# Thermal_Stage_rev4_xml.net
KiCad netlist of a schematic drawn in EAGLE
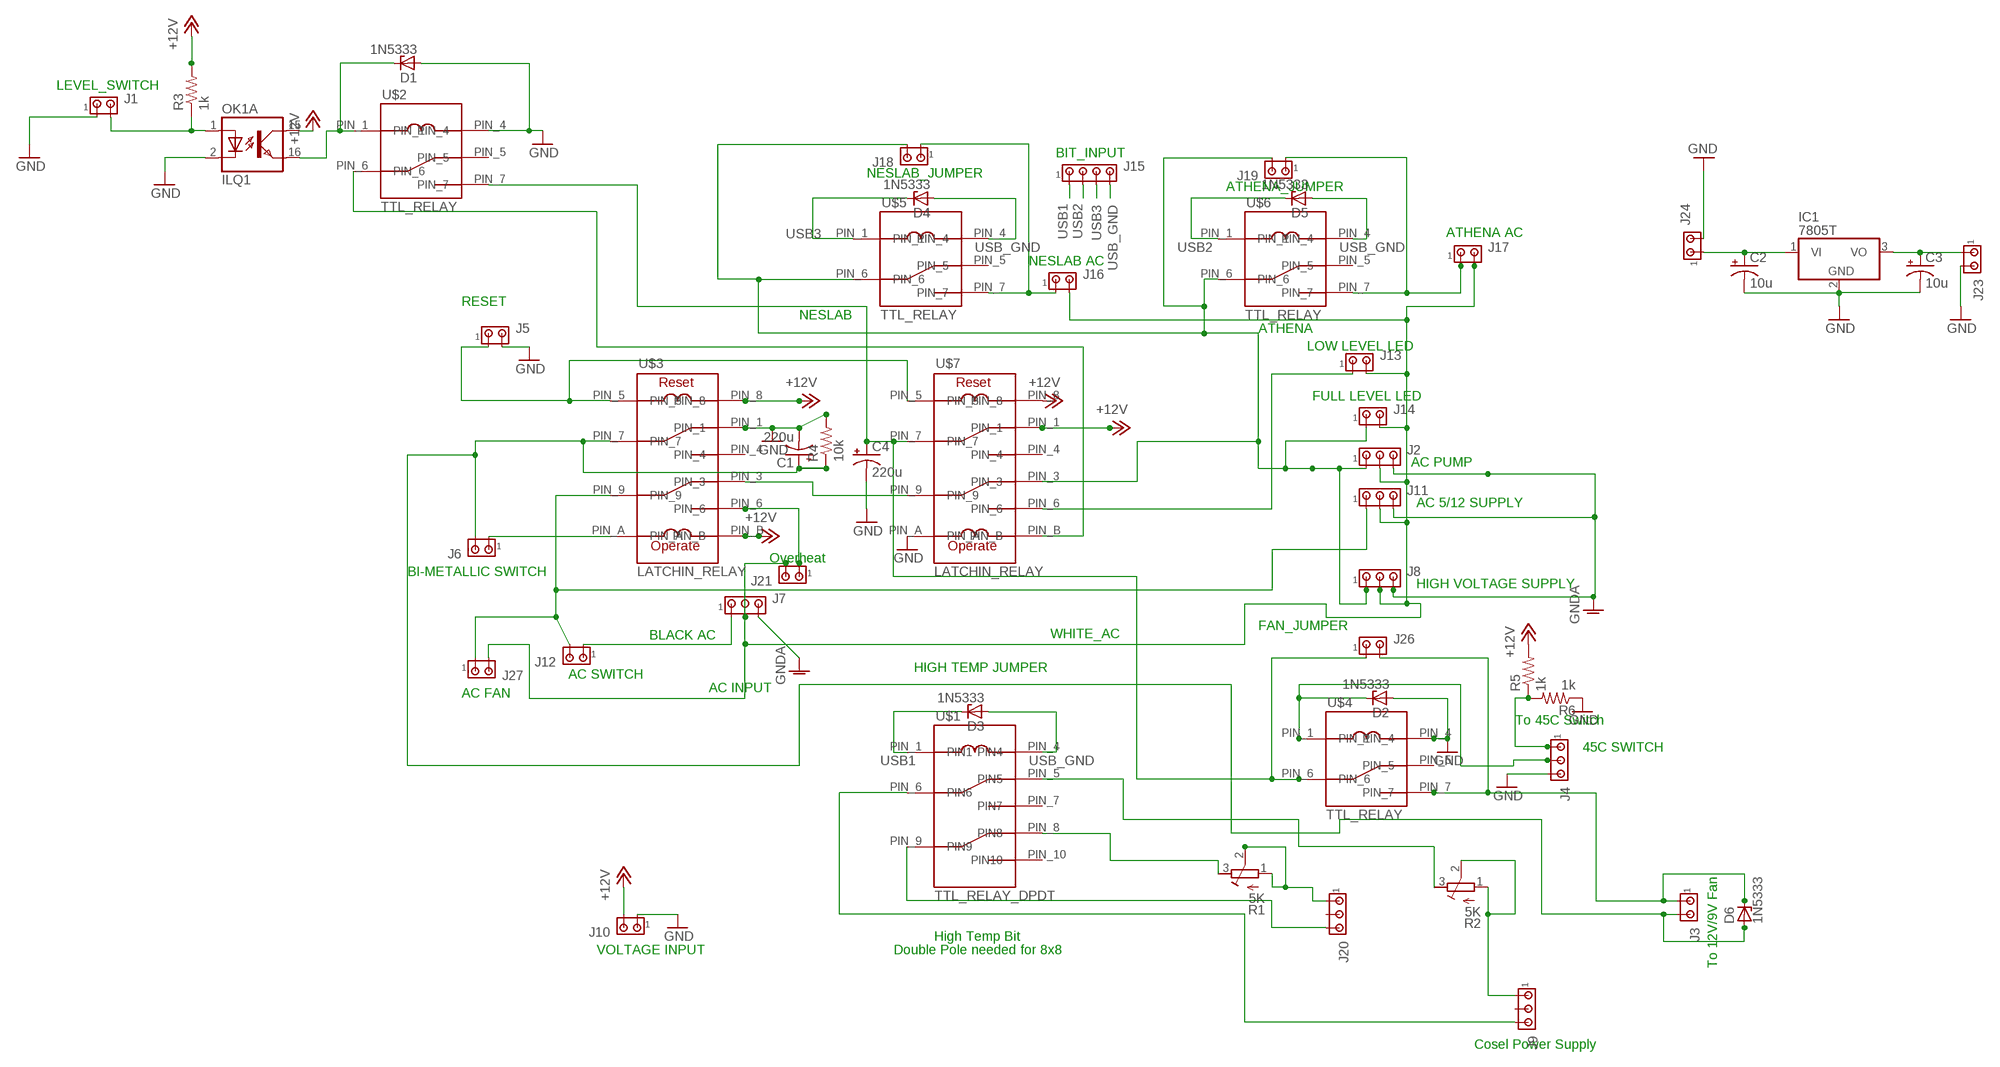
[diagram p0: schematic, sheet 1]

(export (version "E")
  (design (tool "Eeschema 10.0.6"))
  (components
    (comp (ref "C1")
      (value "220u")
      (footprint "eagle-import:E5-13")
      (libsource (lib "eagle-import") (part "CPOL-USE5-13"))
    )
    (comp (ref "C2")
      (value "10u")
      (footprint "eagle-import:E2,5-6E")
      (libsource (lib "eagle-import") (part "CPOL-USE2,5-6E"))
    )
    (comp (ref "C3")
      (value "10u")
      (footprint "eagle-import:E2,5-6E")
      (libsource (lib "eagle-import") (part "CPOL-USE2,5-6E"))
    )
    (comp (ref "C4")
      (value "220u")
      (footprint "eagle-import:E5-13")
      (libsource (lib "eagle-import") (part "CPOL-USE5-13"))
    )
    (comp (ref "D1")
      (value "1N5333")
      (footprint "eagle-import:C1702-15")
      (libsource (lib "eagle-import") (part "1N5333"))
    )
    (comp (ref "D2")
      (value "1N5333")
      (footprint "eagle-import:C1702-15")
      (libsource (lib "eagle-import") (part "1N5333"))
    )
    (comp (ref "D3")
      (value "1N5333")
      (footprint "eagle-import:C1702-15")
      (libsource (lib "eagle-import") (part "1N5333"))
    )
    (comp (ref "D4")
      (value "1N5333")
      (footprint "eagle-import:C1702-15")
      (libsource (lib "eagle-import") (part "1N5333"))
    )
    (comp (ref "D5")
      (value "1N5333")
      (footprint "eagle-import:C1702-15")
      (libsource (lib "eagle-import") (part "1N5333"))
    )
    (comp (ref "D6")
      (value "1N5333")
      (footprint "eagle-import:C1702-15")
      (libsource (lib "eagle-import") (part "1N5333"))
    )
    (comp (ref "IC1")
      (value "7805T")
      (footprint "eagle-import:TO220H")
      (libsource (lib "eagle-import") (part "78T05"))
    )
    (comp (ref "J1")
      (value "MTA02-156")
      (footprint "eagle-import:1X2MTA")
      (libsource (lib "eagle-import") (part "MTA02-156"))
    )
    (comp (ref "J2")
      (value "MTA03-156")
      (footprint "eagle-import:1X3MTA")
      (libsource (lib "eagle-import") (part "MTA03-156"))
    )
    (comp (ref "J3")
      (value "MTA02-156")
      (footprint "eagle-import:1X2MTA")
      (libsource (lib "eagle-import") (part "MTA02-156"))
    )
    (comp (ref "J4")
      (value "MTA03-156")
      (footprint "eagle-import:1X3MTA")
      (libsource (lib "eagle-import") (part "MTA03-156"))
    )
    (comp (ref "J5")
      (value "MTA02-156")
      (footprint "eagle-import:1X2MTA")
      (libsource (lib "eagle-import") (part "MTA02-156"))
    )
    (comp (ref "J6")
      (value "MTA02-156")
      (footprint "eagle-import:1X2MTA")
      (libsource (lib "eagle-import") (part "MTA02-156"))
    )
    (comp (ref "J7")
      (value "MTA03-156")
      (footprint "eagle-import:1X3MTA")
      (libsource (lib "eagle-import") (part "MTA03-156"))
    )
    (comp (ref "J8")
      (value "MTA03-156")
      (footprint "eagle-import:1X3MTA")
      (libsource (lib "eagle-import") (part "MTA03-156"))
    )
    (comp (ref "J9")
      (value "MTA03-100")
      (footprint "eagle-import:10X03MTA")
      (libsource (lib "eagle-import") (part "MTA03-100"))
    )
    (comp (ref "J10")
      (value "MTA02-156")
      (footprint "eagle-import:1X2MTA")
      (libsource (lib "eagle-import") (part "MTA02-156"))
    )
    (comp (ref "J11")
      (value "MTA03-156")
      (footprint "eagle-import:1X3MTA")
      (libsource (lib "eagle-import") (part "MTA03-156"))
    )
    (comp (ref "J12")
      (value "MTA02-156")
      (footprint "eagle-import:1X2MTA")
      (libsource (lib "eagle-import") (part "MTA02-156"))
    )
    (comp (ref "J13")
      (value "MTA02-156")
      (footprint "eagle-import:1X2MTA")
      (libsource (lib "eagle-import") (part "MTA02-156"))
    )
    (comp (ref "J14")
      (value "MTA02-156")
      (footprint "eagle-import:1X2MTA")
      (libsource (lib "eagle-import") (part "MTA02-156"))
    )
    (comp (ref "J15")
      (value "MTA04-100")
      (footprint "eagle-import:10X04MTA")
      (libsource (lib "eagle-import") (part "MTA04-100"))
    )
    (comp (ref "J16")
      (value "MTA02-156")
      (footprint "eagle-import:1X2MTA")
      (libsource (lib "eagle-import") (part "MTA02-156"))
    )
    (comp (ref "J17")
      (value "MTA02-156")
      (footprint "eagle-import:1X2MTA")
      (libsource (lib "eagle-import") (part "MTA02-156"))
    )
    (comp (ref "J18")
      (value "MTA02-100")
      (footprint "eagle-import:10X02MTA")
      (libsource (lib "eagle-import") (part "MTA02-100"))
    )
    (comp (ref "J19")
      (value "MTA02-100")
      (footprint "eagle-import:10X02MTA")
      (libsource (lib "eagle-import") (part "MTA02-100"))
    )
    (comp (ref "J20")
      (value "MTA03-100")
      (footprint "eagle-import:10X03MTA")
      (libsource (lib "eagle-import") (part "MTA03-100"))
    )
    (comp (ref "J21")
      (value "MTA02-156")
      (footprint "eagle-import:1X2MTA")
      (libsource (lib "eagle-import") (part "MTA02-156"))
    )
    (comp (ref "J23")
      (value "MTA02-100")
      (footprint "eagle-import:10X02MTA")
      (libsource (lib "eagle-import") (part "MTA02-100"))
    )
    (comp (ref "J24")
      (value "MTA02-100")
      (footprint "eagle-import:10X02MTA")
      (libsource (lib "eagle-import") (part "MTA02-100"))
    )
    (comp (ref "J26")
      (value "MTA02-100")
      (footprint "eagle-import:10X02MTA")
      (libsource (lib "eagle-import") (part "MTA02-100"))
    )
    (comp (ref "J27")
      (value "MTA02-156")
      (footprint "eagle-import:1X2MTA")
      (libsource (lib "eagle-import") (part "MTA02-156"))
    )
    (comp (ref "OK1")
      (value "ILQ1")
      (footprint "eagle-import:DIL16")
      (libsource (lib "eagle-import") (part "ILQ1"))
    )
    (comp (ref "R1")
      (value "5K")
      (footprint "eagle-import:RTRIM3296W")
      (libsource (lib "eagle-import") (part "R-TRIMM3296W"))
    )
    (comp (ref "R2")
      (value "5K")
      (footprint "eagle-import:RTRIM3296W")
      (libsource (lib "eagle-import") (part "R-TRIMM3296W"))
    )
    (comp (ref "R3")
      (value "1k")
      (footprint "eagle-import:0204_7")
      (libsource (lib "eagle-import") (part "R-US_0204/7"))
    )
    (comp (ref "R4")
      (value "10k")
      (footprint "eagle-import:0204_7")
      (libsource (lib "eagle-import") (part "R-US_0204/7"))
    )
    (comp (ref "R5")
      (value "1k")
      (footprint "eagle-import:0204_7")
      (libsource (lib "eagle-import") (part "R-US_0204/7"))
    )
    (comp (ref "R6")
      (value "1k")
      (footprint "eagle-import:0204_7")
      (libsource (lib "eagle-import") (part "R-US_0204/7"))
    )
    (comp (ref "U$1")
      (value "TTL_RELAY_DPDT")
      (footprint "eagle-import:TTL_RELAY_DPDT")
      (libsource (lib "eagle-import") (part "TTL_RELAY_DPDT"))
    )
    (comp (ref "U$2")
      (value "TTL_RELAY")
      (footprint "eagle-import:R1OS-E1Y1-J1.0K")
      (libsource (lib "eagle-import") (part "TTL_RELAY"))
    )
    (comp (ref "U$3")
      (value "LATCHIN_RELAY")
      (footprint "eagle-import:785XBXCD-12D")
      (libsource (lib "eagle-import") (part "LATCHIN_RELAY"))
    )
    (comp (ref "U$4")
      (value "TTL_RELAY")
      (footprint "eagle-import:R1OS-E1Y1-J1.0K")
      (libsource (lib "eagle-import") (part "TTL_RELAY"))
    )
    (comp (ref "U$5")
      (value "TTL_RELAY")
      (footprint "eagle-import:R1OS-E1Y1-J1.0K")
      (libsource (lib "eagle-import") (part "TTL_RELAY"))
    )
    (comp (ref "U$6")
      (value "TTL_RELAY")
      (footprint "eagle-import:R1OS-E1Y1-J1.0K")
      (libsource (lib "eagle-import") (part "TTL_RELAY"))
    )
    (comp (ref "U$7")
      (value "LATCHIN_RELAY")
      (footprint "eagle-import:785XBXCD-12D")
      (libsource (lib "eagle-import") (part "LATCHIN_RELAY"))
    )
  )
  (nets
    (net (code "1") (name "+12V") (class "Default")
      (node (ref "J10") (pin "2") (pinfunction "2_2") (pintype "passive"))
      (node (ref "OK1") (pin "15") (pinfunction "COL_15") (pintype "passive"))
      (node (ref "R3") (pin "2") (pinfunction "2_2") (pintype "passive"))
      (node (ref "R5") (pin "2") (pinfunction "2_2") (pintype "passive"))
      (node (ref "U$3") (pin "PIN_8") (pinfunction "PIN_8_PIN_8") (pintype "bidirectional"))
      (node (ref "U$3") (pin "PIN_B") (pinfunction "PIN_B_PIN_B") (pintype "bidirectional"))
      (node (ref "U$7") (pin "PIN_1") (pinfunction "PIN_1_PIN_1") (pintype "bidirectional"))
      (node (ref "U$7") (pin "PIN_8") (pinfunction "PIN_8_PIN_8") (pintype "bidirectional"))
    )
    (net (code "2") (name "/USB1") (class "Default")
      (node (ref "D3") (pin "C") (pinfunction "C_C") (pintype "passive"))
      (node (ref "J15") (pin "1") (pinfunction "1_1") (pintype "passive"))
      (node (ref "U$1") (pin "PIN_1") (pinfunction "PIN1_PIN_1") (pintype "bidirectional"))
    )
    (net (code "3") (name "/USB2") (class "Default")
      (node (ref "D5") (pin "C") (pinfunction "C_C") (pintype "passive"))
      (node (ref "J15") (pin "2") (pinfunction "2_2") (pintype "passive"))
      (node (ref "U$6") (pin "PIN_1") (pinfunction "PIN_1_PIN_1") (pintype "bidirectional"))
    )
    (net (code "4") (name "/USB3") (class "Default")
      (node (ref "D4") (pin "C") (pinfunction "C_C") (pintype "passive"))
      (node (ref "J15") (pin "3") (pinfunction "3_3") (pintype "passive"))
      (node (ref "U$5") (pin "PIN_1") (pinfunction "PIN_1_PIN_1") (pintype "bidirectional"))
    )
    (net (code "5") (name "/USB_GND") (class "Default")
      (node (ref "D3") (pin "A") (pinfunction "A_A") (pintype "passive"))
      (node (ref "D4") (pin "A") (pinfunction "A_A") (pintype "passive"))
      (node (ref "D5") (pin "A") (pinfunction "A_A") (pintype "passive"))
      (node (ref "J15") (pin "4") (pinfunction "4_4") (pintype "passive"))
      (node (ref "U$1") (pin "PIN_4") (pinfunction "PIN4_PIN_4") (pintype "bidirectional"))
      (node (ref "U$5") (pin "PIN_4") (pinfunction "PIN_4_PIN_4") (pintype "bidirectional"))
      (node (ref "U$6") (pin "PIN_4") (pinfunction "PIN_4_PIN_4") (pintype "bidirectional"))
    )
    (net (code "6") (name "GND") (class "Default")
      (node (ref "C1") (pin "-") (pinfunction "-_-") (pintype "passive"))
      (node (ref "C2") (pin "-") (pinfunction "-_-") (pintype "passive"))
      (node (ref "C3") (pin "-") (pinfunction "-_-") (pintype "passive"))
      (node (ref "C4") (pin "-") (pinfunction "-_-") (pintype "passive"))
      (node (ref "D1") (pin "A") (pinfunction "A_A") (pintype "passive"))
      (node (ref "D2") (pin "A") (pinfunction "A_A") (pintype "passive"))
      (node (ref "IC1") (pin "2") (pinfunction "GND_2") (pintype "passive"))
      (node (ref "J1") (pin "1") (pinfunction "1_1") (pintype "passive"))
      (node (ref "J10") (pin "1") (pinfunction "1_1") (pintype "passive"))
      (node (ref "J23") (pin "2") (pinfunction "2_2") (pintype "passive"))
      (node (ref "J24") (pin "2") (pinfunction "2_2") (pintype "passive"))
      (node (ref "J4") (pin "3") (pinfunction "3_3") (pintype "passive"))
      (node (ref "J5") (pin "2") (pinfunction "2_2") (pintype "passive"))
      (node (ref "OK1") (pin "2") (pinfunction "C_2") (pintype "passive"))
      (node (ref "R4") (pin "2") (pinfunction "2_2") (pintype "passive"))
      (node (ref "R6") (pin "1") (pinfunction "1_1") (pintype "passive"))
      (node (ref "U$2") (pin "PIN_4") (pinfunction "PIN_4_PIN_4") (pintype "bidirectional"))
      (node (ref "U$3") (pin "PIN_1") (pinfunction "PIN_1_PIN_1") (pintype "bidirectional"))
      (node (ref "U$4") (pin "PIN_4") (pinfunction "PIN_4_PIN_4") (pintype "bidirectional"))
      (node (ref "U$7") (pin "PIN_A") (pinfunction "PIN_A_PIN_A") (pintype "bidirectional"))
    )
    (net (code "7") (name "GNDA") (class "Default")
      (node (ref "J11") (pin "3") (pinfunction "3_3") (pintype "passive"))
      (node (ref "J2") (pin "3") (pinfunction "3_3") (pintype "passive"))
      (node (ref "J7") (pin "3") (pinfunction "3_3") (pintype "passive"))
      (node (ref "J8") (pin "3") (pinfunction "3_3") (pintype "passive"))
    )
    (net (code "8") (name "Net-(C1-Pad+)") (class "Default")
      (node (ref "C1") (pin "+") (pinfunction "+_+") (pintype "passive"))
      (node (ref "D6") (pin "A") (pinfunction "A_A") (pintype "passive"))
      (node (ref "J3") (pin "2") (pinfunction "2_2") (pintype "passive"))
      (node (ref "J6") (pin "2") (pinfunction "2_2") (pintype "passive"))
      (node (ref "R4") (pin "1") (pinfunction "1_1") (pintype "passive"))
      (node (ref "U$3") (pin "PIN_7") (pinfunction "PIN_7_PIN_7") (pintype "bidirectional"))
    )
    (net (code "9") (name "Net-(C4-Pad+)") (class "Default")
      (node (ref "C4") (pin "+") (pinfunction "+_+") (pintype "passive"))
      (node (ref "J26") (pin "1") (pinfunction "1_1") (pintype "passive"))
      (node (ref "U$2") (pin "PIN_7") (pinfunction "PIN_7_PIN_7") (pintype "bidirectional"))
      (node (ref "U$4") (pin "PIN_6") (pinfunction "PIN_6_PIN_6") (pintype "bidirectional"))
      (node (ref "U$7") (pin "PIN_7") (pinfunction "PIN_7_PIN_7") (pintype "bidirectional"))
    )
    (net (code "10") (name "Net-(D2-PadC)") (class "Default")
      (node (ref "D2") (pin "C") (pinfunction "C_C") (pintype "passive"))
      (node (ref "J4") (pin "2") (pinfunction "2_2") (pintype "passive"))
      (node (ref "U$4") (pin "PIN_1") (pinfunction "PIN_1_PIN_1") (pintype "bidirectional"))
    )
    (net (code "11") (name "Net-(D6-PadC)") (class "Default")
      (node (ref "D6") (pin "C") (pinfunction "C_C") (pintype "passive"))
      (node (ref "J26") (pin "2") (pinfunction "2_2") (pintype "passive"))
      (node (ref "J3") (pin "1") (pinfunction "1_1") (pintype "passive"))
      (node (ref "U$4") (pin "PIN_7") (pinfunction "PIN_7_PIN_7") (pintype "bidirectional"))
    )
    (net (code "12") (name "Net-(IC1-VI)") (class "Default")
      (node (ref "C2") (pin "+") (pinfunction "+_+") (pintype "passive"))
      (node (ref "IC1") (pin "1") (pinfunction "VI_1") (pintype "input"))
      (node (ref "J24") (pin "1") (pinfunction "1_1") (pintype "passive"))
    )
    (net (code "13") (name "Net-(IC1-VO)") (class "Default")
      (node (ref "C3") (pin "+") (pinfunction "+_+") (pintype "passive"))
      (node (ref "IC1") (pin "3") (pinfunction "VO_3") (pintype "passive"))
      (node (ref "J23") (pin "1") (pinfunction "1_1") (pintype "passive"))
    )
    (net (code "14") (name "Net-(J4-Pad1)") (class "Default")
      (node (ref "J4") (pin "1") (pinfunction "1_1") (pintype "passive"))
      (node (ref "R5") (pin "1") (pinfunction "1_1") (pintype "passive"))
      (node (ref "R6") (pin "2") (pinfunction "2_2") (pintype "passive"))
    )
    (net (code "15") (name "Net-(J5-Pad1)") (class "Default")
      (node (ref "J5") (pin "1") (pinfunction "1_1") (pintype "passive"))
      (node (ref "U$3") (pin "PIN_5") (pinfunction "PIN_5_PIN_5") (pintype "bidirectional"))
      (node (ref "U$7") (pin "PIN_5") (pinfunction "PIN_5_PIN_5") (pintype "bidirectional"))
    )
    (net (code "16") (name "Net-(J6-Pad1)") (class "Default")
      (node (ref "J6") (pin "1") (pinfunction "1_1") (pintype "passive"))
      (node (ref "U$3") (pin "PIN_A") (pinfunction "PIN_A_PIN_A") (pintype "bidirectional"))
    )
    (net (code "17") (name "Net-(J11-Pad1)") (class "Default")
      (node (ref "J11") (pin "1") (pinfunction "1_1") (pintype "passive"))
      (node (ref "J12") (pin "2") (pinfunction "2_2") (pintype "passive"))
      (node (ref "J27") (pin "1") (pinfunction "1_1") (pintype "passive"))
      (node (ref "U$3") (pin "PIN_9") (pinfunction "PIN_9_PIN_9") (pintype "bidirectional"))
    )
    (net (code "18") (name "Net-(J11-Pad2)") (class "Default")
      (node (ref "J11") (pin "2") (pinfunction "2_2") (pintype "passive"))
      (node (ref "J13") (pin "2") (pinfunction "2_2") (pintype "passive"))
      (node (ref "J14") (pin "2") (pinfunction "2_2") (pintype "passive"))
      (node (ref "J16") (pin "2") (pinfunction "2_2") (pintype "passive"))
      (node (ref "J17") (pin "2") (pinfunction "2_2") (pintype "passive"))
      (node (ref "J2") (pin "2") (pinfunction "2_2") (pintype "passive"))
      (node (ref "J21") (pin "2") (pinfunction "2_2") (pintype "passive"))
      (node (ref "J27") (pin "2") (pinfunction "2_2") (pintype "passive"))
      (node (ref "J7") (pin "2") (pinfunction "2_2") (pintype "passive"))
      (node (ref "J8") (pin "2") (pinfunction "2_2") (pintype "passive"))
    )
    (net (code "19") (name "Net-(J12-Pad1)") (class "Default")
      (node (ref "J12") (pin "1") (pinfunction "1_1") (pintype "passive"))
      (node (ref "J7") (pin "1") (pinfunction "1_1") (pintype "passive"))
    )
    (net (code "20") (name "Net-(J13-Pad1)") (class "Default")
      (node (ref "J13") (pin "1") (pinfunction "1_1") (pintype "passive"))
      (node (ref "U$7") (pin "PIN_6") (pinfunction "PIN_6_PIN_6") (pintype "bidirectional"))
    )
    (net (code "21") (name "Net-(J14-Pad1)") (class "Default")
      (node (ref "J14") (pin "1") (pinfunction "1_1") (pintype "passive"))
      (node (ref "J18") (pin "2") (pinfunction "2_2") (pintype "passive"))
      (node (ref "J19") (pin "2") (pinfunction "2_2") (pintype "passive"))
      (node (ref "J2") (pin "1") (pinfunction "1_1") (pintype "passive"))
      (node (ref "J8") (pin "1") (pinfunction "1_1") (pintype "passive"))
      (node (ref "U$5") (pin "PIN_6") (pinfunction "PIN_6_PIN_6") (pintype "bidirectional"))
      (node (ref "U$6") (pin "PIN_6") (pinfunction "PIN_6_PIN_6") (pintype "bidirectional"))
      (node (ref "U$7") (pin "PIN_3") (pinfunction "PIN_3_PIN_3") (pintype "bidirectional"))
    )
    (net (code "22") (name "Net-(J16-Pad1)") (class "Default")
      (node (ref "J16") (pin "1") (pinfunction "1_1") (pintype "passive"))
      (node (ref "J18") (pin "1") (pinfunction "1_1") (pintype "passive"))
      (node (ref "U$5") (pin "PIN_7") (pinfunction "PIN_7_PIN_7") (pintype "bidirectional"))
    )
    (net (code "23") (name "Net-(J17-Pad1)") (class "Default")
      (node (ref "J17") (pin "1") (pinfunction "1_1") (pintype "passive"))
      (node (ref "J19") (pin "1") (pinfunction "1_1") (pintype "passive"))
      (node (ref "U$6") (pin "PIN_7") (pinfunction "PIN_7_PIN_7") (pintype "bidirectional"))
    )
    (net (code "24") (name "Net-(J21-Pad1)") (class "Default")
      (node (ref "J21") (pin "1") (pinfunction "1_1") (pintype "passive"))
      (node (ref "U$3") (pin "PIN_6") (pinfunction "PIN_6_PIN_6") (pintype "bidirectional"))
    )
    (net (code "25") (name "Net-(OK1A-A)") (class "Default")
      (node (ref "J1") (pin "2") (pinfunction "2_2") (pintype "passive"))
      (node (ref "OK1") (pin "1") (pinfunction "A_1") (pintype "passive"))
      (node (ref "R3") (pin "1") (pinfunction "1_1") (pintype "passive"))
    )
    (net (code "26") (name "Net-(OK1A-EMIT)") (class "Default")
      (node (ref "D1") (pin "C") (pinfunction "C_C") (pintype "passive"))
      (node (ref "OK1") (pin "16") (pinfunction "EMIT_16") (pintype "passive"))
      (node (ref "U$2") (pin "PIN_1") (pinfunction "PIN_1_PIN_1") (pintype "bidirectional"))
    )
    (net (code "27") (name "Net-(R1-A)") (class "Default")
      (node (ref "R1") (pin "3") (pinfunction "A_3") (pintype "passive"))
      (node (ref "U$1") (pin "PIN_8") (pinfunction "PIN8_PIN_8") (pintype "bidirectional"))
    )
    (net (code "28") (name "Net-(R1-E)") (class "Default")
      (node (ref "J20") (pin "1") (pinfunction "1_1") (pintype "passive"))
      (node (ref "R1") (pin "1") (pinfunction "E_1") (pintype "passive"))
      (node (ref "R1") (pin "2") (pinfunction "S_2") (pintype "passive"))
    )
    (net (code "29") (name "Net-(R2-A)") (class "Default")
      (node (ref "R2") (pin "3") (pinfunction "A_3") (pintype "passive"))
      (node (ref "U$1") (pin "PIN_5") (pinfunction "PIN5_PIN_5") (pintype "bidirectional"))
    )
    (net (code "30") (name "Net-(R2-E)") (class "Default")
      (node (ref "J9") (pin "1") (pinfunction "1_1") (pintype "passive"))
      (node (ref "R2") (pin "1") (pinfunction "E_1") (pintype "passive"))
      (node (ref "R2") (pin "2") (pinfunction "S_2") (pintype "passive"))
    )
    (net (code "31") (name "Net-(U$1-PIN6)") (class "Default")
      (node (ref "J9") (pin "3") (pinfunction "3_3") (pintype "passive"))
      (node (ref "U$1") (pin "PIN_6") (pinfunction "PIN6_PIN_6") (pintype "bidirectional"))
    )
    (net (code "32") (name "Net-(U$1-PIN9)") (class "Default")
      (node (ref "J20") (pin "3") (pinfunction "3_3") (pintype "passive"))
      (node (ref "U$1") (pin "PIN_9") (pinfunction "PIN9_PIN_9") (pintype "bidirectional"))
    )
    (net (code "33") (name "Net-(U$2-PadPIN_6)") (class "Default")
      (node (ref "U$2") (pin "PIN_6") (pinfunction "PIN_6_PIN_6") (pintype "bidirectional"))
      (node (ref "U$7") (pin "PIN_B") (pinfunction "PIN_B_PIN_B") (pintype "bidirectional"))
    )
    (net (code "34") (name "Net-(U$3-PadPIN_3)") (class "Default")
      (node (ref "U$3") (pin "PIN_3") (pinfunction "PIN_3_PIN_3") (pintype "bidirectional"))
      (node (ref "U$7") (pin "PIN_9") (pinfunction "PIN_9_PIN_9") (pintype "bidirectional"))
    )
    (net (code "35") (name "unconnected-(J9-Pad2)") (class "Default")
      (node (ref "J9") (pin "2") (pinfunction "2_2") (pintype "passive"))
    )
    (net (code "36") (name "unconnected-(J20-Pad2)") (class "Default")
      (node (ref "J20") (pin "2") (pinfunction "2_2") (pintype "passive"))
    )
    (net (code "37") (name "unconnected-(U$1-PIN7-PadPIN_7)") (class "Default")
      (node (ref "U$1") (pin "PIN_7") (pinfunction "PIN7_PIN_7") (pintype "bidirectional"))
    )
    (net (code "38") (name "unconnected-(U$1-PIN10-PadPIN_10)") (class "Default")
      (node (ref "U$1") (pin "PIN_10") (pinfunction "PIN10_PIN_10") (pintype "bidirectional"))
    )
    (net (code "39") (name "unconnected-(U$2-PadPIN_5)") (class "Default")
      (node (ref "U$2") (pin "PIN_5") (pinfunction "PIN_5_PIN_5") (pintype "bidirectional"))
    )
    (net (code "40") (name "unconnected-(U$3-PadPIN_4)") (class "Default")
      (node (ref "U$3") (pin "PIN_4") (pinfunction "PIN_4_PIN_4") (pintype "bidirectional"))
    )
    (net (code "41") (name "unconnected-(U$4-PadPIN_5)") (class "Default")
      (node (ref "U$4") (pin "PIN_5") (pinfunction "PIN_5_PIN_5") (pintype "bidirectional"))
    )
    (net (code "42") (name "unconnected-(U$5-PadPIN_5)") (class "Default")
      (node (ref "U$5") (pin "PIN_5") (pinfunction "PIN_5_PIN_5") (pintype "bidirectional"))
    )
    (net (code "43") (name "unconnected-(U$6-PadPIN_5)") (class "Default")
      (node (ref "U$6") (pin "PIN_5") (pinfunction "PIN_5_PIN_5") (pintype "bidirectional"))
    )
    (net (code "44") (name "unconnected-(U$7-PadPIN_4)") (class "Default")
      (node (ref "U$7") (pin "PIN_4") (pinfunction "PIN_4_PIN_4") (pintype "bidirectional"))
    )
  )
)
